# SNAC_7ch_SMS_DB9_3D.net
KiCad netlist of a schematic drawn in EAGLE
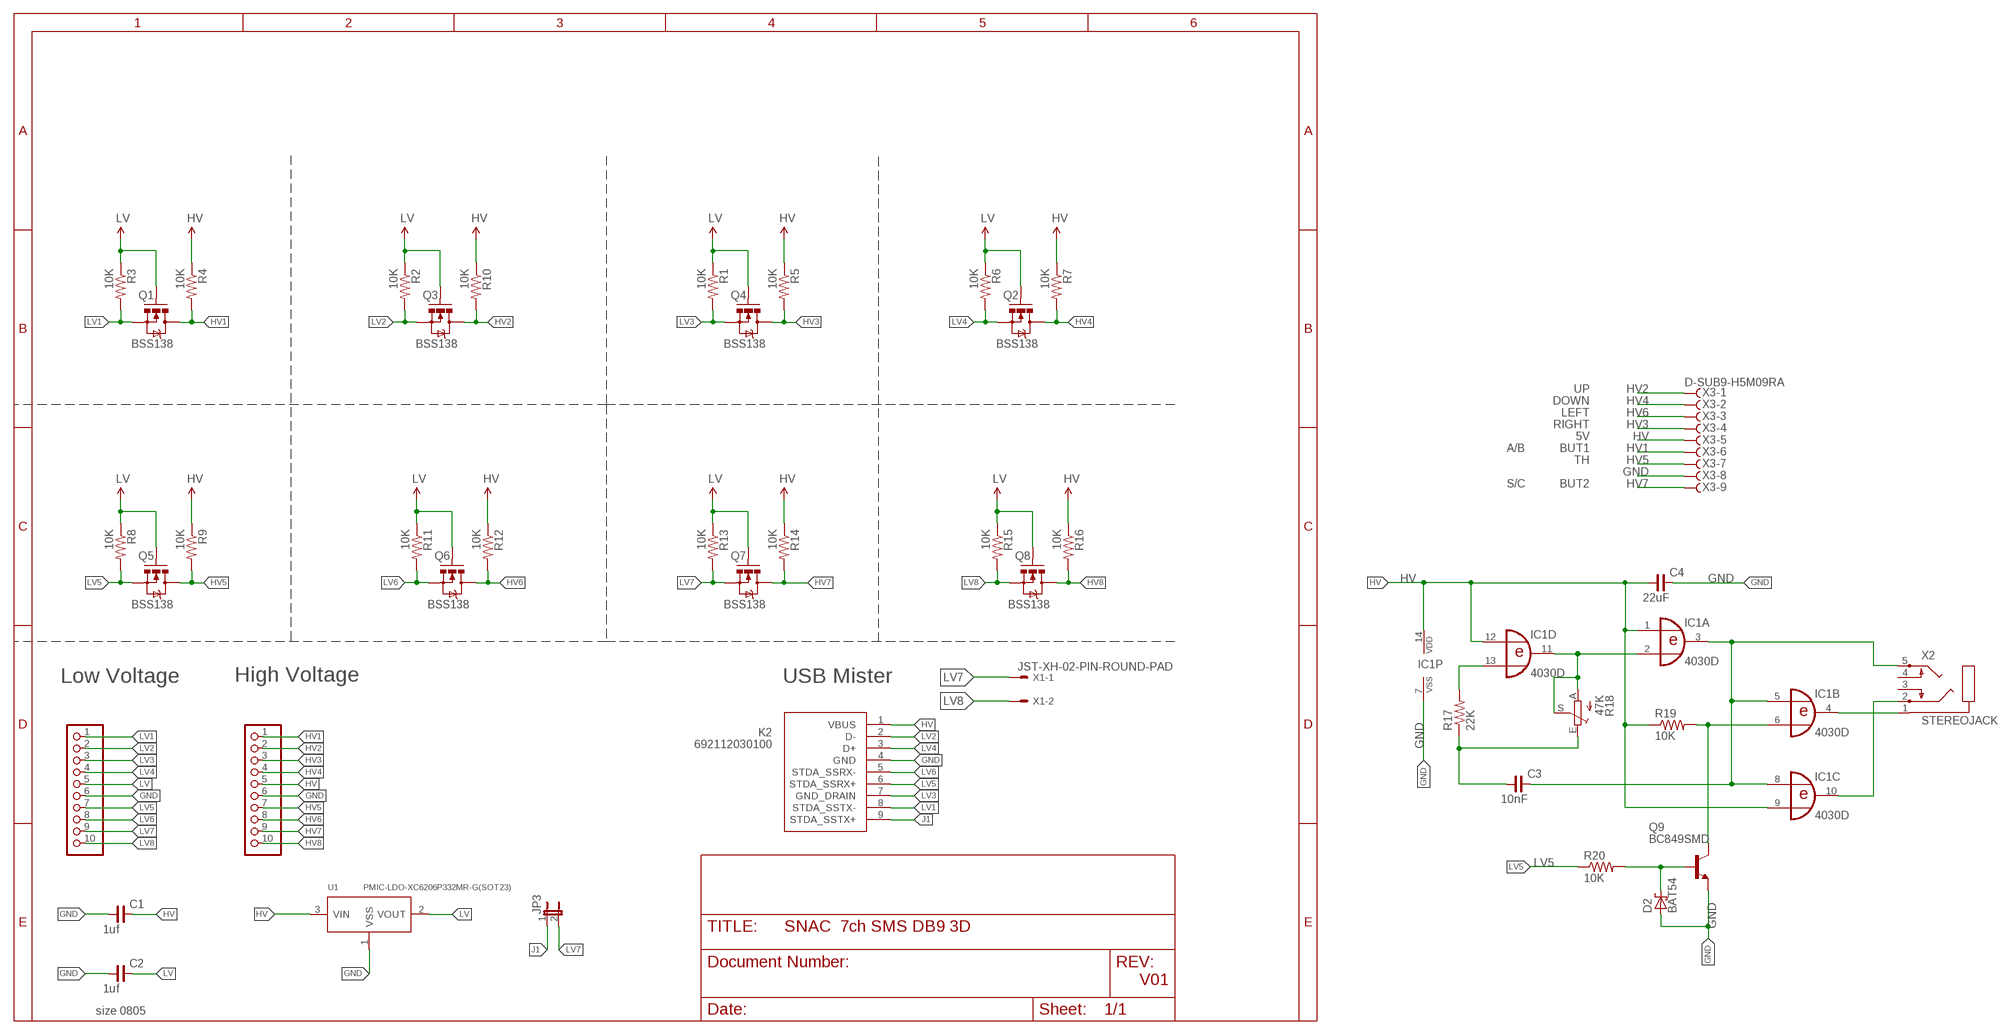
[diagram p0: schematic, sheet 1]

(export (version "E")
  (design (tool "Eeschema 10.0.6"))
  (components
    (comp (ref "C1")
      (value "1uf")
      (footprint "eagle-import:C0805")
      (libsource (lib "eagle-import") (part "C_0805"))
    )
    (comp (ref "C2")
      (value "1uf")
      (footprint "eagle-import:C0805")
      (libsource (lib "eagle-import") (part "C_0805"))
    )
    (comp (ref "C3")
      (value "10nF")
      (footprint "eagle-import:C0805")
      (libsource (lib "eagle-import") (part "C_0805"))
    )
    (comp (ref "C4")
      (value "22uF")
      (footprint "eagle-import:C0805")
      (libsource (lib "eagle-import") (part "C_0805"))
    )
    (comp (ref "D2")
      (value "BAT54")
      (footprint "eagle-import:SOT23")
      (libsource (lib "eagle-import") (part "BAT54"))
    )
    (comp (ref "IC1")
      (value "4030D")
      (footprint "eagle-import:SO14")
      (libsource (lib "eagle-import") (part "4030D"))
    )
    (comp (ref "JP1")
      (value "PINHD-1X10_2.54-S")
      (footprint "eagle-import:1X10-S")
      (libsource (lib "eagle-import") (part "PINHD-1X10_2.54-S"))
    )
    (comp (ref "JP2")
      (value "PINHD-1X10_2.54-S")
      (footprint "eagle-import:1X10-S")
      (libsource (lib "eagle-import") (part "PINHD-1X10_2.54-S"))
    )
    (comp (ref "JP3")
      (value "JUMPER-2PTH")
      (footprint "eagle-import:1X02")
      (libsource (lib "eagle-import") (part "JUMPER-2PTH"))
    )
    (comp (ref "K2")
      (value "692112030100")
      (footprint "eagle-import:692112030100")
      (libsource (lib "eagle-import") (part "692112030100"))
    )
    (comp (ref "Q1")
      (value "BSS138")
      (footprint "eagle-import:SOT23-3")
      (libsource (lib "eagle-import") (part "MOSFET-NCHANNELSMD"))
    )
    (comp (ref "Q2")
      (value "BSS138")
      (footprint "eagle-import:SOT23-3")
      (libsource (lib "eagle-import") (part "MOSFET-NCHANNELSMD"))
    )
    (comp (ref "Q3")
      (value "BSS138")
      (footprint "eagle-import:SOT23-3")
      (libsource (lib "eagle-import") (part "MOSFET-NCHANNELSMD"))
    )
    (comp (ref "Q4")
      (value "BSS138")
      (footprint "eagle-import:SOT23-3")
      (libsource (lib "eagle-import") (part "MOSFET-NCHANNELSMD"))
    )
    (comp (ref "Q5")
      (value "BSS138")
      (footprint "eagle-import:SOT23-3")
      (libsource (lib "eagle-import") (part "MOSFET-NCHANNELSMD"))
    )
    (comp (ref "Q6")
      (value "BSS138")
      (footprint "eagle-import:SOT23-3")
      (libsource (lib "eagle-import") (part "MOSFET-NCHANNELSMD"))
    )
    (comp (ref "Q7")
      (value "BSS138")
      (footprint "eagle-import:SOT23-3")
      (libsource (lib "eagle-import") (part "MOSFET-NCHANNELSMD"))
    )
    (comp (ref "Q8")
      (value "BSS138")
      (footprint "eagle-import:SOT23-3")
      (libsource (lib "eagle-import") (part "MOSFET-NCHANNELSMD"))
    )
    (comp (ref "Q9")
      (value "BC849SMD")
      (footprint "eagle-import:SOT23-BEC")
      (libsource (lib "eagle-import") (part "BC849SMD"))
    )
    (comp (ref "R1")
      (value "10K")
      (footprint "eagle-import:0603-RES")
      (libsource (lib "eagle-import") (part "RESISTOR0603-RES"))
    )
    (comp (ref "R2")
      (value "10K")
      (footprint "eagle-import:0603-RES")
      (libsource (lib "eagle-import") (part "RESISTOR0603-RES"))
    )
    (comp (ref "R3")
      (value "10K")
      (footprint "eagle-import:0603-RES")
      (libsource (lib "eagle-import") (part "RESISTOR0603-RES"))
    )
    (comp (ref "R4")
      (value "10K")
      (footprint "eagle-import:0603-RES")
      (libsource (lib "eagle-import") (part "RESISTOR0603-RES"))
    )
    (comp (ref "R5")
      (value "10K")
      (footprint "eagle-import:0603-RES")
      (libsource (lib "eagle-import") (part "RESISTOR0603-RES"))
    )
    (comp (ref "R6")
      (value "10K")
      (footprint "eagle-import:0603-RES")
      (libsource (lib "eagle-import") (part "RESISTOR0603-RES"))
    )
    (comp (ref "R7")
      (value "10K")
      (footprint "eagle-import:0603-RES")
      (libsource (lib "eagle-import") (part "RESISTOR0603-RES"))
    )
    (comp (ref "R8")
      (value "10K")
      (footprint "eagle-import:0603-RES")
      (libsource (lib "eagle-import") (part "RESISTOR0603-RES"))
    )
    (comp (ref "R9")
      (value "10K")
      (footprint "eagle-import:0603-RES")
      (libsource (lib "eagle-import") (part "RESISTOR0603-RES"))
    )
    (comp (ref "R10")
      (value "10K")
      (footprint "eagle-import:0603-RES")
      (libsource (lib "eagle-import") (part "RESISTOR0603-RES"))
    )
    (comp (ref "R11")
      (value "10K")
      (footprint "eagle-import:0603-RES")
      (libsource (lib "eagle-import") (part "RESISTOR0603-RES"))
    )
    (comp (ref "R12")
      (value "10K")
      (footprint "eagle-import:0603-RES")
      (libsource (lib "eagle-import") (part "RESISTOR0603-RES"))
    )
    (comp (ref "R13")
      (value "10K")
      (footprint "eagle-import:0603-RES")
      (libsource (lib "eagle-import") (part "RESISTOR0603-RES"))
    )
    (comp (ref "R14")
      (value "10K")
      (footprint "eagle-import:0603-RES")
      (libsource (lib "eagle-import") (part "RESISTOR0603-RES"))
    )
    (comp (ref "R15")
      (value "10K")
      (footprint "eagle-import:0603-RES")
      (libsource (lib "eagle-import") (part "RESISTOR0603-RES"))
    )
    (comp (ref "R16")
      (value "10K")
      (footprint "eagle-import:0603-RES")
      (libsource (lib "eagle-import") (part "RESISTOR0603-RES"))
    )
    (comp (ref "R17")
      (value "22K")
      (footprint "eagle-import:0603-RES")
      (libsource (lib "eagle-import") (part "RESISTOR0603-RES"))
    )
    (comp (ref "R18")
      (value "47K")
      (footprint "eagle-import:B25P")
      (libsource (lib "eagle-import") (part "TRIM_EU-B25P"))
    )
    (comp (ref "R19")
      (value "10K")
      (footprint "eagle-import:0603-RES")
      (libsource (lib "eagle-import") (part "RESISTOR0603-RES"))
    )
    (comp (ref "R20")
      (value "10K")
      (footprint "eagle-import:0603-RES")
      (libsource (lib "eagle-import") (part "RESISTOR0603-RES"))
    )
    (comp (ref "U1")
      (value "PMIC-LDO-XC6206P332MR-G(SOT23)")
      (footprint "eagle-import:SOT-23")
      (fields (field (name "MF") "Torex") (field (name "MP") "XC6206P332MR-G"))
      (libsource (lib "eagle-import") (part "PMIC-LDO-XC6206P332MR-G(SOT23)"))
    )
    (comp (ref "X1")
      (value "JST-XH-02-PIN-ROUND-PAD")
      (footprint "eagle-import:JST-XH-02-PACKAGE-ROUND-PAD")
      (libsource (lib "eagle-import") (part "JST-XH-02-PIN-ROUND-PAD"))
    )
    (comp (ref "X2")
      (value "STEREOJACK")
      (footprint "eagle-import:STX3100")
      (libsource (lib "eagle-import") (part "STEREOJACK"))
    )
    (comp (ref "X3")
      (value "D-SUB9-H5M09RA")
      (footprint "eagle-import:H5M09RA")
      (libsource (lib "eagle-import") (part "D-SUB9-H5M09RA"))
    )
  )
  (nets
    (net (code "1") (name "GND") (class "Default")
      (node (ref "C1") (pin "1") (pinfunction "1_1") (pintype "passive"))
      (node (ref "C2") (pin "1") (pinfunction "1_1") (pintype "passive"))
      (node (ref "C4") (pin "2") (pinfunction "2_2") (pintype "passive"))
      (node (ref "D2") (pin "1") (pinfunction "A_1") (pintype "passive"))
      (node (ref "IC1") (pin "7") (pinfunction "VSS_7") (pintype "power_in"))
      (node (ref "JP1") (pin "6") (pinfunction "6_6") (pintype "passive"))
      (node (ref "JP2") (pin "6") (pinfunction "6_6") (pintype "passive"))
      (node (ref "K2") (pin "4") (pinfunction "GND_4") (pintype "bidirectional"))
      (node (ref "Q9") (pin "E") (pinfunction "E_E") (pintype "passive"))
      (node (ref "U1") (pin "1") (pinfunction "VSS_1") (pintype "power_in"))
      (node (ref "X3") (pin "8") (pinfunction "F_8") (pintype "passive"))
    )
    (net (code "2") (name "HV") (class "Default")
      (node (ref "C1") (pin "2") (pinfunction "2_2") (pintype "passive"))
      (node (ref "C4") (pin "1") (pinfunction "1_1") (pintype "passive"))
      (node (ref "IC1") (pin "1") (pinfunction "I0_1") (pintype "input"))
      (node (ref "IC1") (pin "12") (pinfunction "I0_12") (pintype "input"))
      (node (ref "IC1") (pin "14") (pinfunction "VDD_14") (pintype "power_in"))
      (node (ref "IC1") (pin "9") (pinfunction "I1_9") (pintype "input"))
      (node (ref "JP2") (pin "5") (pinfunction "5_5") (pintype "passive"))
      (node (ref "K2") (pin "1") (pinfunction "VBUS_1") (pintype "bidirectional"))
      (node (ref "R10") (pin "1") (pinfunction "1_1") (pintype "passive"))
      (node (ref "R12") (pin "1") (pinfunction "1_1") (pintype "passive"))
      (node (ref "R14") (pin "1") (pinfunction "1_1") (pintype "passive"))
      (node (ref "R16") (pin "1") (pinfunction "1_1") (pintype "passive"))
      (node (ref "R19") (pin "1") (pinfunction "1_1") (pintype "passive"))
      (node (ref "R4") (pin "1") (pinfunction "1_1") (pintype "passive"))
      (node (ref "R5") (pin "1") (pinfunction "1_1") (pintype "passive"))
      (node (ref "R7") (pin "1") (pinfunction "1_1") (pintype "passive"))
      (node (ref "R9") (pin "1") (pinfunction "1_1") (pintype "passive"))
      (node (ref "U1") (pin "3") (pinfunction "VIN_3") (pintype "input"))
      (node (ref "X3") (pin "5") (pinfunction "F_5") (pintype "passive"))
    )
    (net (code "3") (name "HV1") (class "Default")
      (node (ref "JP2") (pin "1") (pinfunction "1_1") (pintype "passive"))
      (node (ref "Q1") (pin "3") (pinfunction "D_3") (pintype "passive"))
      (node (ref "R4") (pin "2") (pinfunction "2_2") (pintype "passive"))
      (node (ref "X3") (pin "6") (pinfunction "F_6") (pintype "passive"))
    )
    (net (code "4") (name "HV2") (class "Default")
      (node (ref "JP2") (pin "2") (pinfunction "2_2") (pintype "passive"))
      (node (ref "Q3") (pin "3") (pinfunction "D_3") (pintype "passive"))
      (node (ref "R10") (pin "2") (pinfunction "2_2") (pintype "passive"))
      (node (ref "X3") (pin "1") (pinfunction "F_1") (pintype "passive"))
    )
    (net (code "5") (name "HV3") (class "Default")
      (node (ref "JP2") (pin "3") (pinfunction "3_3") (pintype "passive"))
      (node (ref "Q4") (pin "3") (pinfunction "D_3") (pintype "passive"))
      (node (ref "R5") (pin "2") (pinfunction "2_2") (pintype "passive"))
      (node (ref "X3") (pin "4") (pinfunction "F_4") (pintype "passive"))
    )
    (net (code "6") (name "HV4") (class "Default")
      (node (ref "JP2") (pin "4") (pinfunction "4_4") (pintype "passive"))
      (node (ref "Q2") (pin "3") (pinfunction "D_3") (pintype "passive"))
      (node (ref "R7") (pin "2") (pinfunction "2_2") (pintype "passive"))
      (node (ref "X3") (pin "2") (pinfunction "F_2") (pintype "passive"))
    )
    (net (code "7") (name "HV5") (class "Default")
      (node (ref "JP2") (pin "7") (pinfunction "7_7") (pintype "passive"))
      (node (ref "Q5") (pin "3") (pinfunction "D_3") (pintype "passive"))
      (node (ref "R9") (pin "2") (pinfunction "2_2") (pintype "passive"))
      (node (ref "X3") (pin "7") (pinfunction "F_7") (pintype "passive"))
    )
    (net (code "8") (name "HV6") (class "Default")
      (node (ref "JP2") (pin "8") (pinfunction "8_8") (pintype "passive"))
      (node (ref "Q6") (pin "3") (pinfunction "D_3") (pintype "passive"))
      (node (ref "R12") (pin "2") (pinfunction "2_2") (pintype "passive"))
      (node (ref "X3") (pin "3") (pinfunction "F_3") (pintype "passive"))
    )
    (net (code "9") (name "HV7") (class "Default")
      (node (ref "JP2") (pin "9") (pinfunction "9_9") (pintype "passive"))
      (node (ref "Q7") (pin "3") (pinfunction "D_3") (pintype "passive"))
      (node (ref "R14") (pin "2") (pinfunction "2_2") (pintype "passive"))
      (node (ref "X3") (pin "9") (pinfunction "F_9") (pintype "passive"))
    )
    (net (code "10") (name "HV8") (class "Default")
      (node (ref "JP2") (pin "10") (pinfunction "10_10") (pintype "passive"))
      (node (ref "Q8") (pin "3") (pinfunction "D_3") (pintype "passive"))
      (node (ref "R16") (pin "2") (pinfunction "2_2") (pintype "passive"))
    )
    (net (code "11") (name "J1") (class "Default")
      (node (ref "JP3") (pin "1") (pinfunction "1_1") (pintype "passive"))
      (node (ref "K2") (pin "9") (pinfunction "STDA_SSTX+_9") (pintype "bidirectional"))
    )
    (net (code "12") (name "LV") (class "Default")
      (node (ref "C2") (pin "2") (pinfunction "2_2") (pintype "passive"))
      (node (ref "JP1") (pin "5") (pinfunction "5_5") (pintype "passive"))
      (node (ref "Q1") (pin "1") (pinfunction "G_1") (pintype "passive"))
      (node (ref "Q2") (pin "1") (pinfunction "G_1") (pintype "passive"))
      (node (ref "Q3") (pin "1") (pinfunction "G_1") (pintype "passive"))
      (node (ref "Q4") (pin "1") (pinfunction "G_1") (pintype "passive"))
      (node (ref "Q5") (pin "1") (pinfunction "G_1") (pintype "passive"))
      (node (ref "Q6") (pin "1") (pinfunction "G_1") (pintype "passive"))
      (node (ref "Q7") (pin "1") (pinfunction "G_1") (pintype "passive"))
      (node (ref "Q8") (pin "1") (pinfunction "G_1") (pintype "passive"))
      (node (ref "R1") (pin "1") (pinfunction "1_1") (pintype "passive"))
      (node (ref "R11") (pin "1") (pinfunction "1_1") (pintype "passive"))
      (node (ref "R13") (pin "1") (pinfunction "1_1") (pintype "passive"))
      (node (ref "R15") (pin "1") (pinfunction "1_1") (pintype "passive"))
      (node (ref "R2") (pin "1") (pinfunction "1_1") (pintype "passive"))
      (node (ref "R3") (pin "1") (pinfunction "1_1") (pintype "passive"))
      (node (ref "R6") (pin "1") (pinfunction "1_1") (pintype "passive"))
      (node (ref "R8") (pin "1") (pinfunction "1_1") (pintype "passive"))
      (node (ref "U1") (pin "2") (pinfunction "VOUT_2") (pintype "output"))
    )
    (net (code "13") (name "LV1") (class "Default")
      (node (ref "JP1") (pin "1") (pinfunction "1_1") (pintype "passive"))
      (node (ref "K2") (pin "8") (pinfunction "STDA_SSTX-_8") (pintype "bidirectional"))
      (node (ref "Q1") (pin "2") (pinfunction "S_2") (pintype "passive"))
      (node (ref "R3") (pin "2") (pinfunction "2_2") (pintype "passive"))
    )
    (net (code "14") (name "LV2") (class "Default")
      (node (ref "JP1") (pin "2") (pinfunction "2_2") (pintype "passive"))
      (node (ref "K2") (pin "2") (pinfunction "D-_2") (pintype "bidirectional"))
      (node (ref "Q3") (pin "2") (pinfunction "S_2") (pintype "passive"))
      (node (ref "R2") (pin "2") (pinfunction "2_2") (pintype "passive"))
    )
    (net (code "15") (name "LV3") (class "Default")
      (node (ref "JP1") (pin "3") (pinfunction "3_3") (pintype "passive"))
      (node (ref "K2") (pin "7") (pinfunction "GND_DRAIN_7") (pintype "bidirectional"))
      (node (ref "Q4") (pin "2") (pinfunction "S_2") (pintype "passive"))
      (node (ref "R1") (pin "2") (pinfunction "2_2") (pintype "passive"))
    )
    (net (code "16") (name "LV4") (class "Default")
      (node (ref "JP1") (pin "4") (pinfunction "4_4") (pintype "passive"))
      (node (ref "K2") (pin "3") (pinfunction "D+_3") (pintype "bidirectional"))
      (node (ref "Q2") (pin "2") (pinfunction "S_2") (pintype "passive"))
      (node (ref "R6") (pin "2") (pinfunction "2_2") (pintype "passive"))
    )
    (net (code "17") (name "LV5") (class "Default")
      (node (ref "JP1") (pin "7") (pinfunction "7_7") (pintype "passive"))
      (node (ref "K2") (pin "6") (pinfunction "STDA_SSRX+_6") (pintype "bidirectional"))
      (node (ref "Q5") (pin "2") (pinfunction "S_2") (pintype "passive"))
      (node (ref "R20") (pin "1") (pinfunction "1_1") (pintype "passive"))
      (node (ref "R8") (pin "2") (pinfunction "2_2") (pintype "passive"))
    )
    (net (code "18") (name "LV6") (class "Default")
      (node (ref "JP1") (pin "8") (pinfunction "8_8") (pintype "passive"))
      (node (ref "K2") (pin "5") (pinfunction "STDA_SSRX-_5") (pintype "bidirectional"))
      (node (ref "Q6") (pin "2") (pinfunction "S_2") (pintype "passive"))
      (node (ref "R11") (pin "2") (pinfunction "2_2") (pintype "passive"))
    )
    (net (code "19") (name "LV7") (class "Default")
      (node (ref "JP1") (pin "9") (pinfunction "9_9") (pintype "passive"))
      (node (ref "JP3") (pin "2") (pinfunction "2_2") (pintype "passive"))
      (node (ref "Q7") (pin "2") (pinfunction "S_2") (pintype "passive"))
      (node (ref "R13") (pin "2") (pinfunction "2_2") (pintype "passive"))
      (node (ref "X1") (pin "1") (pinfunction "S_1") (pintype "passive"))
    )
    (net (code "20") (name "LV8") (class "Default")
      (node (ref "JP1") (pin "10") (pinfunction "10_10") (pintype "passive"))
      (node (ref "Q8") (pin "2") (pinfunction "S_2") (pintype "passive"))
      (node (ref "R15") (pin "2") (pinfunction "2_2") (pintype "passive"))
      (node (ref "X1") (pin "2") (pinfunction "S_2") (pintype "passive"))
    )
    (net (code "21") (name "Net-(C3-Pad1)") (class "Default")
      (node (ref "C3") (pin "1") (pinfunction "1_1") (pintype "passive"))
      (node (ref "R17") (pin "1") (pinfunction "1_1") (pintype "passive"))
      (node (ref "R18") (pin "E") (pinfunction "E_E") (pintype "passive"))
    )
    (net (code "22") (name "Net-(D2-C)") (class "Default")
      (node (ref "D2") (pin "3") (pinfunction "C_3") (pintype "passive"))
      (node (ref "Q9") (pin "B") (pinfunction "B_B") (pintype "passive"))
      (node (ref "R20") (pin "2") (pinfunction "2_2") (pintype "passive"))
    )
    (net (code "23") (name "Net-(IC1A-I1)") (class "Default")
      (node (ref "IC1") (pin "11") (pinfunction "O_11") (pintype "output"))
      (node (ref "IC1") (pin "2") (pinfunction "I1_2") (pintype "input"))
      (node (ref "R18") (pin "A") (pinfunction "A_A") (pintype "passive"))
      (node (ref "R18") (pin "S") (pinfunction "S_S") (pintype "passive"))
    )
    (net (code "24") (name "Net-(IC1A-O)") (class "Default")
      (node (ref "C3") (pin "2") (pinfunction "2_2") (pintype "passive"))
      (node (ref "IC1") (pin "3") (pinfunction "O_3") (pintype "output"))
      (node (ref "IC1") (pin "5") (pinfunction "I0_5") (pintype "input"))
      (node (ref "IC1") (pin "8") (pinfunction "I0_8") (pintype "input"))
      (node (ref "X2") (pin "5") (pinfunction "5_5") (pintype "passive"))
    )
    (net (code "25") (name "Net-(IC1B-I1)") (class "Default")
      (node (ref "IC1") (pin "6") (pinfunction "I1_6") (pintype "input"))
      (node (ref "Q9") (pin "C") (pinfunction "C_C") (pintype "passive"))
      (node (ref "R19") (pin "2") (pinfunction "2_2") (pintype "passive"))
    )
    (net (code "26") (name "Net-(IC1B-O)") (class "Default")
      (node (ref "IC1") (pin "4") (pinfunction "O_4") (pintype "output"))
      (node (ref "X2") (pin "1") (pinfunction "1_1") (pintype "passive"))
    )
    (net (code "27") (name "Net-(IC1C-O)") (class "Default")
      (node (ref "IC1") (pin "10") (pinfunction "O_10") (pintype "output"))
      (node (ref "X2") (pin "2") (pinfunction "2_2") (pintype "passive"))
    )
    (net (code "28") (name "Net-(IC1D-I1)") (class "Default")
      (node (ref "IC1") (pin "13") (pinfunction "I1_13") (pintype "input"))
      (node (ref "R17") (pin "2") (pinfunction "2_2") (pintype "passive"))
    )
    (net (code "29") (name "unconnected-(X2-Pad3)") (class "Default")
      (node (ref "X2") (pin "3") (pinfunction "3_3") (pintype "passive"))
    )
    (net (code "30") (name "unconnected-(X2-Pad4)") (class "Default")
      (node (ref "X2") (pin "4") (pinfunction "4_4") (pintype "passive"))
    )
  )
)
